# ProPrj_1-Schematic_NFC_PCB_Card_2026-05-.net
KiCad netlist of a schematic drawn in EasyEDA Pro
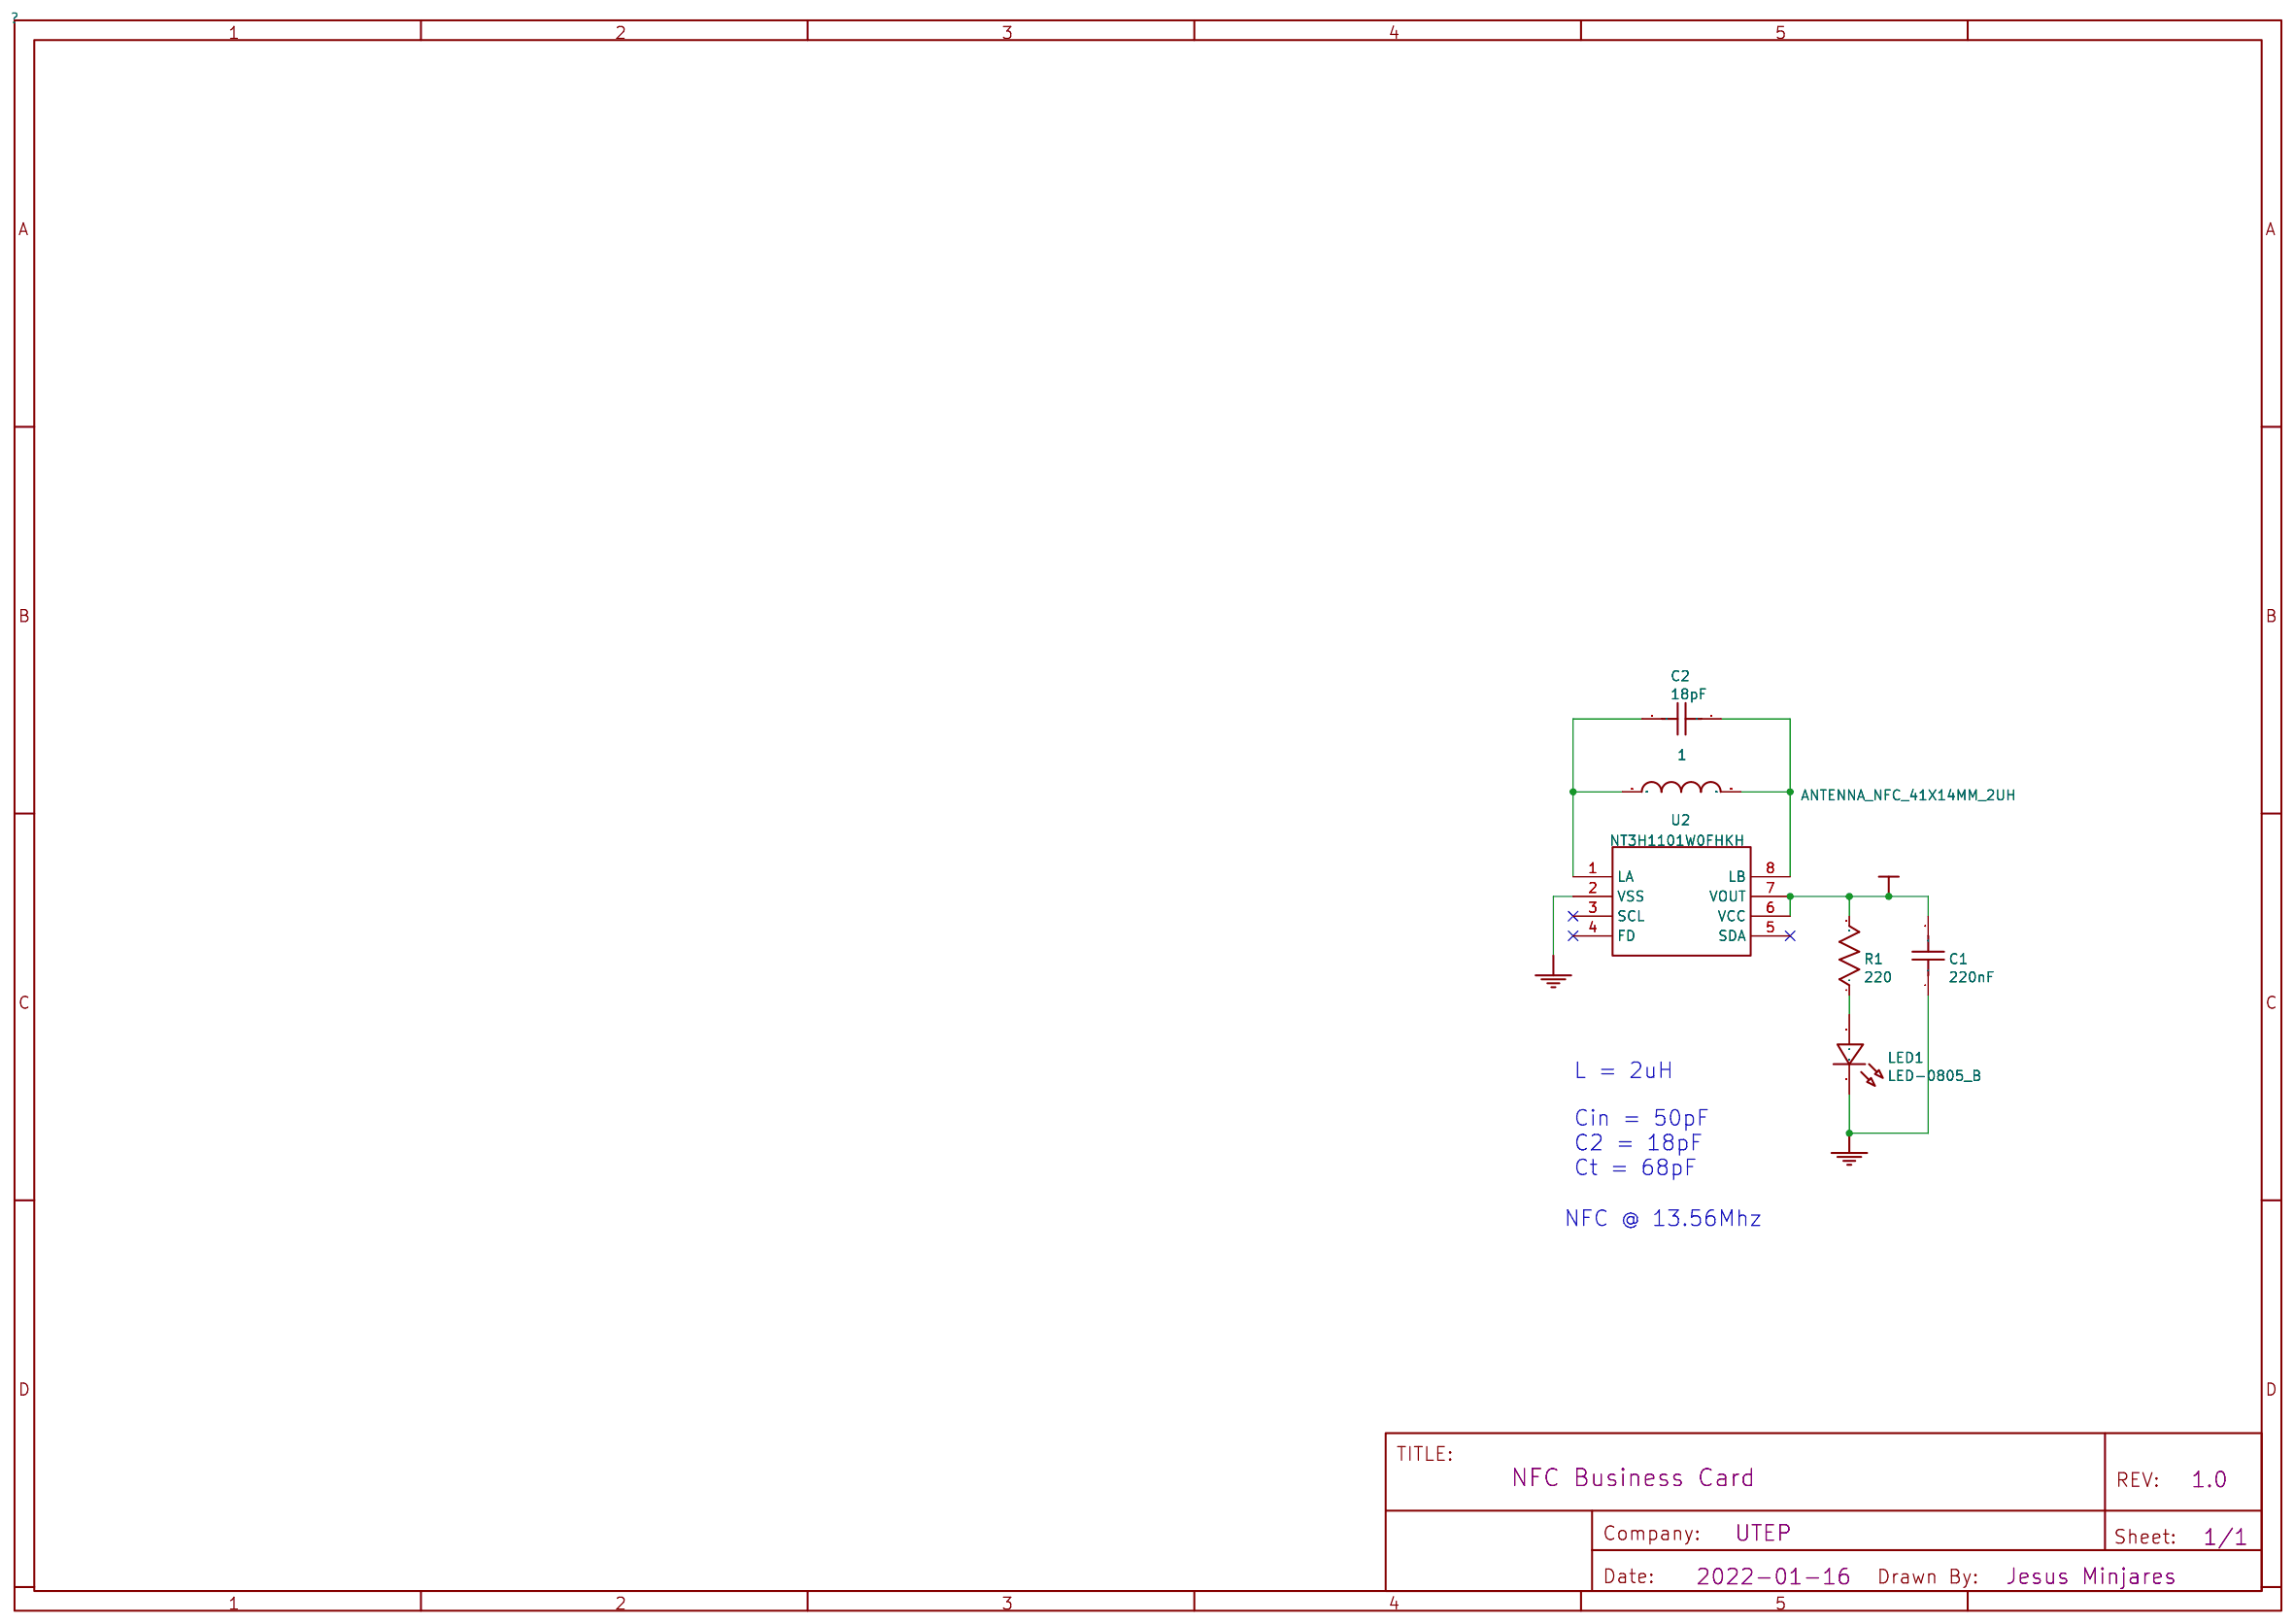
[diagram p0: schematic sheet]

(export (version "E")
  (design (tool "Eeschema 10.0.6"))
  (components
    (comp (ref "1")
      (value "ANTENNA_NFC_41X14MM_2UH")
      (fields (field (name "Contributor") "Dan Schnur"))
      (libsource (lib "easyedapro") (part "ANTENNA_NFC_41X14MM_2UH"))
    )
    (comp (ref "C1")
      (value "220nF")
      (fields (field (name "Contributor") "LCEDA_Lib"))
      (libsource (lib "easyedapro") (part "220nF"))
    )
    (comp (ref "C2")
      (value "18pF")
      (fields (field (name "Contributor") "LCEDA_Lib"))
      (libsource (lib "easyedapro") (part "18pF"))
    )
    (comp (ref "LED1")
      (value "LED-0805_B")
      (fields
        (field (name "Manufacturer Part") "D-B080508B1-KS2")
        (field (name "Manufacturer") "方舟 ARKLED")
        (field (name "Contributor") "LCEDA_Lib")
      )
      (libsource (lib "easyedapro") (part "LED-0805_B"))
    )
    (comp (ref "R1")
      (value "220")
      (fields (field (name "Contributor") "LCEDA_Lib"))
      (libsource (lib "easyedapro") (part "220"))
    )
    (comp (ref "U2")
      (value "NT3H1101W0FHKH")
      (fields (field (name "Manufacturer") "NXP Semicon") (field (name "Contributor") "LCSC"))
      (libsource (lib "easyedapro") (part "NT3H1101W0FHKH"))
    )
  )
  (nets
    (net (code "1") (name "GND") (class "Default")
      (node (ref "C1") (pin "1") (pinfunction "1_1") (pintype "unspecified"))
      (node (ref "LED1") (pin "2") (pinfunction "2_2") (pintype "unspecified"))
      (node (ref "U2") (pin "2") (pinfunction "VSS_2") (pintype "unspecified"))
    )
    (net (code "2") (name "Net-(LED1-Pad1)") (class "Default")
      (node (ref "LED1") (pin "1") (pinfunction "1_1") (pintype "unspecified"))
      (node (ref "R1") (pin "1") (pinfunction "1_1") (pintype "unspecified"))
    )
    (net (code "3") (name "Net-(U2-LA)") (class "Default")
      (node (ref "1") (pin "P$1") (pinfunction "P$1_P$1") (pintype "bidirectional"))
      (node (ref "C2") (pin "1") (pinfunction "1_1") (pintype "unspecified"))
      (node (ref "U2") (pin "1") (pinfunction "LA_1") (pintype "unspecified"))
    )
    (net (code "4") (name "Net-(U2-LB)") (class "Default")
      (node (ref "1") (pin "P$2") (pinfunction "P$2_P$2") (pintype "bidirectional"))
      (node (ref "C2") (pin "2") (pinfunction "2_2") (pintype "unspecified"))
      (node (ref "U2") (pin "8") (pinfunction "LB_8") (pintype "unspecified"))
    )
    (net (code "5") (name "VCC") (class "Default")
      (node (ref "C1") (pin "2") (pinfunction "2_2") (pintype "unspecified"))
      (node (ref "R1") (pin "2") (pinfunction "2_2") (pintype "unspecified"))
      (node (ref "U2") (pin "6") (pinfunction "VCC_6") (pintype "unspecified"))
      (node (ref "U2") (pin "7") (pinfunction "VOUT_7") (pintype "unspecified"))
    )
    (net (code "6") (name "unconnected-(U2-FD-Pad4)") (class "Default")
      (node (ref "U2") (pin "4") (pinfunction "FD_4") (pintype "unspecified+no_connect"))
    )
    (net (code "7") (name "unconnected-(U2-SCL-Pad3)") (class "Default")
      (node (ref "U2") (pin "3") (pinfunction "SCL_3") (pintype "unspecified+no_connect"))
    )
    (net (code "8") (name "unconnected-(U2-SDA-Pad5)") (class "Default")
      (node (ref "U2") (pin "5") (pinfunction "SDA_5") (pintype "unspecified+no_connect"))
    )
  )
)
